# OpenSourceSyringePump.net
KiCad netlist of a schematic drawn in EAGLE
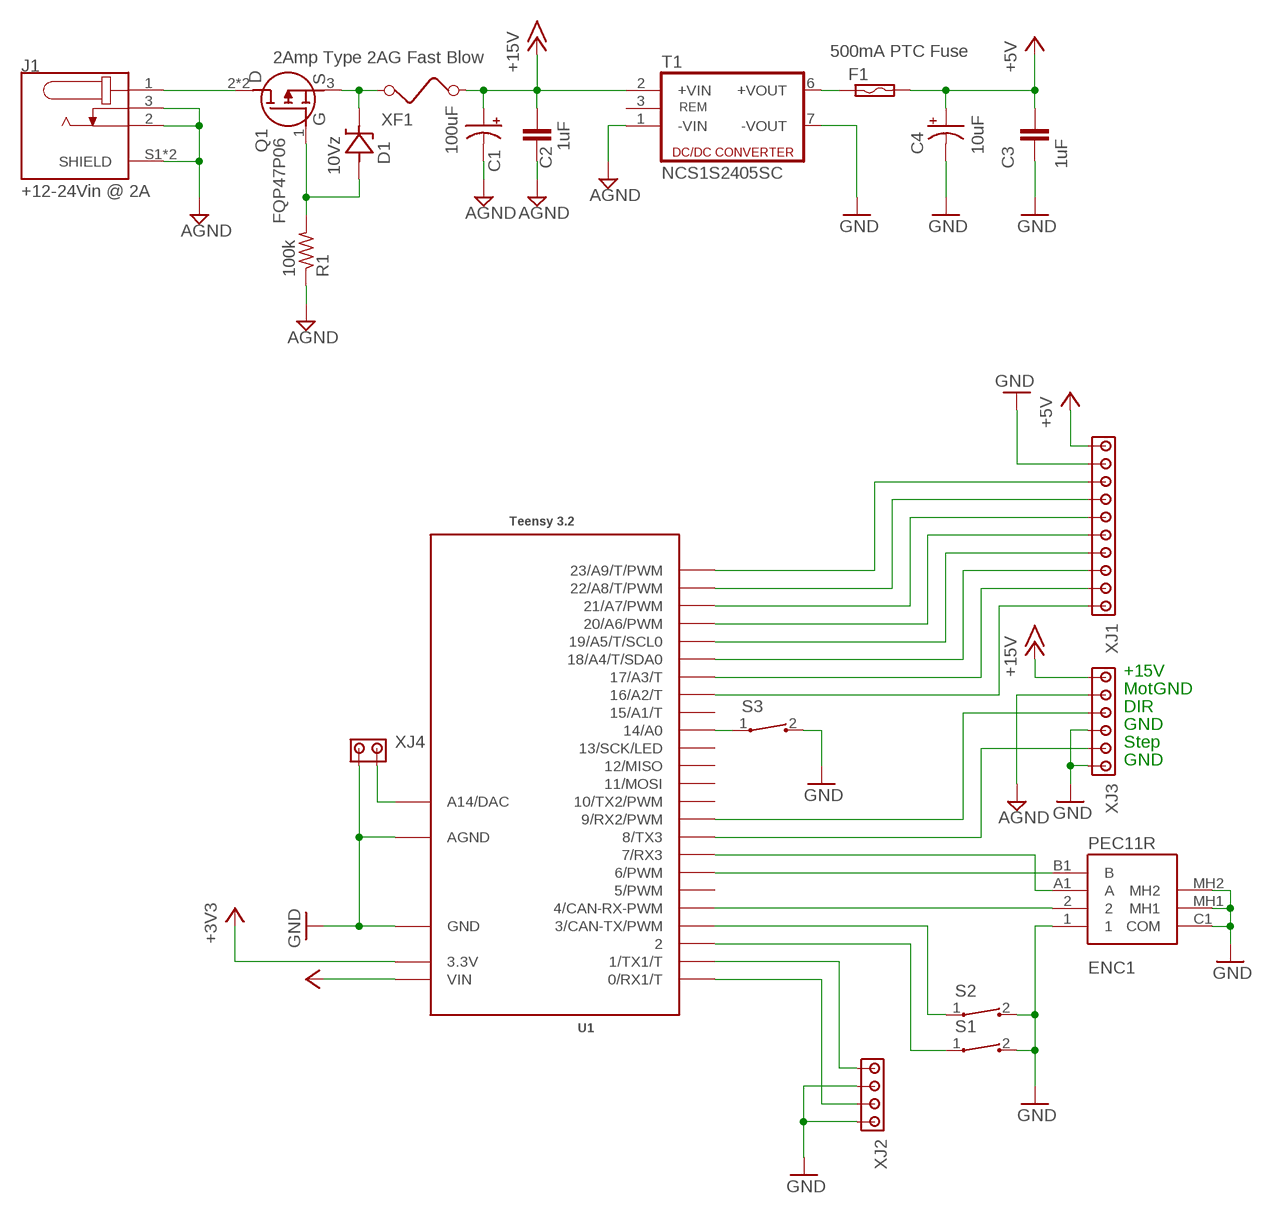
[diagram p0: schematic, sheet 1]

(export (version "E")
  (design (tool "Eeschema 10.0.6"))
  (components
    (comp (ref "C1")
      (value "100uF")
      (footprint "eagle-import:EEUFR1H101")
      (libsource (lib "eagle-import") (part "EEUFR1H101"))
    )
    (comp (ref "C2")
      (value "1uF")
      (footprint "eagle-import:K105Z20Y5VF5TL2")
      (libsource (lib "eagle-import") (part "K105Z20Y5VF5TL2"))
    )
    (comp (ref "C3")
      (value "1uF")
      (footprint "eagle-import:K105Z20Y5VF5TL2")
      (libsource (lib "eagle-import") (part "K105Z20Y5VF5TL2"))
    )
    (comp (ref "C4")
      (value "10uF")
      (footprint "eagle-import:TAP106K025SCS")
      (libsource (lib "eagle-import") (part "TAP106K025SCS"))
    )
    (comp (ref "D1")
      (value "10Vz")
      (footprint "eagle-import:BZX79C10")
      (libsource (lib "eagle-import") (part "BZX79C10"))
    )
    (comp (ref "ENC1")
      (value "PEC11R")
      (footprint "eagle-import:PEC11R4220FS0024")
      (fields
        (field (name "MANUFACTURER_PART_NUMBER") "PEC11R-4220F-S0024")
        (field (name "MOUSER_PART_NUMBER") "652-PEC11R-4220F-S24")
      )
      (libsource (lib "eagle-import") (part "PEC11R-4220F-S0024"))
    )
    (comp (ref "F1")
      (value "500mA PTC Fuse")
      (footprint "eagle-import:BOURNS-MF-R025")
      (libsource (lib "eagle-import") (part "BOURNS-MF-R025"))
    )
    (comp (ref "J1")
      (value "+12-24Vin @ 2A")
      (footprint "eagle-import:CUI_PJ-079AH")
      (fields (field (name "MANUFACTURER") "CUI Inc"))
      (libsource (lib "eagle-import") (part "PJ-079AH"))
    )
    (comp (ref "Q1")
      (value "FQP47P06")
      (footprint "eagle-import:FQP47P06")
      (libsource (lib "eagle-import") (part "FQP47P06"))
    )
    (comp (ref "R1")
      (value "100k")
      (footprint "eagle-import:0204_7")
      (libsource (lib "eagle-import") (part "RESISTOR.25W"))
    )
    (comp (ref "S1")
      (value "ALPS-SKRGAFD010")
      (footprint "eagle-import:ALPS-SKRGAFD010")
      (libsource (lib "eagle-import") (part "ALPS-SKRGAFD010"))
    )
    (comp (ref "S2")
      (value "ALPS-SKRGAFD010")
      (footprint "eagle-import:ALPS-SKRGAFD010")
      (libsource (lib "eagle-import") (part "ALPS-SKRGAFD010"))
    )
    (comp (ref "S3")
      (value "ALPS-SKRGAFD010")
      (footprint "eagle-import:ALPS-SKRGAFD010")
      (libsource (lib "eagle-import") (part "ALPS-SKRGAFD010"))
    )
    (comp (ref "T1")
      (value "NCS1S2405SC")
      (footprint "eagle-import:MURATA-NCS1S2405SC")
      (libsource (lib "eagle-import") (part "MURATA-NCS1S2405SC"))
    )
    (comp (ref "U1")
      (value "Teensy 3.2")
      (footprint "eagle-import:TEENSY_3.0-3.2&LC_OUTER_ROW")
      (libsource (lib "eagle-import") (part "TEENSY_3.1-3.2_OUTER_ROW"))
    )
    (comp (ref "XF1")
      (value "2Amp Type 2AG Fast Blow")
      (footprint "eagle-import:LITTLEFUSE-02540101Z")
      (libsource (lib "eagle-import") (part "LITTLEFUSE-02540101Z"))
    )
    (comp (ref "XJ1")
      (value "TE-1-282834-0-DOUBLE")
      (footprint "eagle-import:TE-1-282834-0-DOUBLE")
      (libsource (lib "eagle-import") (part "TE-1-282834-0-DOUBLE"))
    )
    (comp (ref "XJ2")
      (value "TE-282834-4-DOUBLE")
      (footprint "eagle-import:TE-282834-4-DOUBLE")
      (libsource (lib "eagle-import") (part "TE-282834-4-DOUBLE"))
    )
    (comp (ref "XJ3")
      (value "TE-282834-6-DOUBLE")
      (footprint "eagle-import:TE-282834-6-DOUBLE")
      (libsource (lib "eagle-import") (part "TE-282834-6-DOUBLE"))
    )
    (comp (ref "XJ4")
      (value "TE-282834-2-DOUBLE")
      (footprint "eagle-import:TE-282834-2-DOUBLE")
      (libsource (lib "eagle-import") (part "TE-282834-2-DOUBLE"))
    )
  )
  (nets
    (net (code "1") (name "+3V3") (class "Default")
      (node (ref "U1") (pin "3.3V") (pinfunction "3.3V_3.3V") (pintype "power_in"))
    )
    (net (code "2") (name "+5V") (class "Default")
      (node (ref "C3") (pin "1") (pinfunction "1_1") (pintype "passive"))
      (node (ref "C4") (pin "+") (pinfunction "+_+") (pintype "passive"))
      (node (ref "F1") (pin "2") (pinfunction "2_2") (pintype "passive"))
      (node (ref "U1") (pin "VIN") (pinfunction "VIN_VIN") (pintype "power_in"))
      (node (ref "XJ1") (pin "1") (pinfunction "1_1") (pintype "passive"))
      (node (ref "XJ1") (pin "P$1") (pinfunction "1_P$1") (pintype "passive"))
    )
    (net (code "3") (name "+15V") (class "Default")
      (node (ref "C1") (pin "+") (pinfunction "+_+") (pintype "passive"))
      (node (ref "C2") (pin "1") (pinfunction "1_1") (pintype "passive"))
      (node (ref "T1") (pin "2") (pinfunction "+VIN_2") (pintype "power_in"))
      (node (ref "XF1") (pin "1") (pinfunction "1_1") (pintype "passive"))
      (node (ref "XJ3") (pin "1") (pinfunction "1_1") (pintype "passive"))
      (node (ref "XJ3") (pin "P$1") (pinfunction "1_P$1") (pintype "passive"))
    )
    (net (code "4") (name "AGND") (class "Default")
      (node (ref "C1") (pin "-") (pinfunction "-_-") (pintype "passive"))
      (node (ref "C2") (pin "2") (pinfunction "2_2") (pintype "passive"))
      (node (ref "J1") (pin "2") (pinfunction "2_2") (pintype "passive"))
      (node (ref "J1") (pin "3") (pinfunction "3_3") (pintype "passive"))
      (node (ref "J1") (pin "S1") (pinfunction "SHIELD_S1") (pintype "passive"))
      (node (ref "J1") (pin "S2") (pinfunction "SHIELD_S2") (pintype "passive"))
      (node (ref "R1") (pin "1") (pinfunction "1_1") (pintype "passive"))
      (node (ref "T1") (pin "1") (pinfunction "-VIN_1") (pintype "power_in"))
      (node (ref "XJ3") (pin "2") (pinfunction "2_2") (pintype "passive"))
      (node (ref "XJ3") (pin "P$2") (pinfunction "2_P$2") (pintype "passive"))
    )
    (net (code "5") (name "GND") (class "Default")
      (node (ref "C3") (pin "2") (pinfunction "2_2") (pintype "passive"))
      (node (ref "C4") (pin "-") (pinfunction "-_-") (pintype "passive"))
      (node (ref "ENC1") (pin "1") (pinfunction "1_1") (pintype "bidirectional"))
      (node (ref "ENC1") (pin "C1") (pinfunction "COM_C1") (pintype "power_in"))
      (node (ref "ENC1") (pin "MH1") (pinfunction "MH1_MH1") (pintype "bidirectional"))
      (node (ref "ENC1") (pin "MH2") (pinfunction "MH2_MH2") (pintype "bidirectional"))
      (node (ref "S1") (pin "2") (pinfunction "2_2") (pintype "passive"))
      (node (ref "S2") (pin "2") (pinfunction "2_2") (pintype "passive"))
      (node (ref "S3") (pin "2") (pinfunction "2_2") (pintype "passive"))
      (node (ref "T1") (pin "7") (pinfunction "-VOUT_7") (pintype "power_in"))
      (node (ref "U1") (pin "AGND") (pinfunction "AGND_AGND") (pintype "power_in"))
      (node (ref "U1") (pin "GND") (pinfunction "GND_GND") (pintype "power_in"))
      (node (ref "XJ1") (pin "2") (pinfunction "2_2") (pintype "passive"))
      (node (ref "XJ1") (pin "P$2") (pinfunction "2_P$2") (pintype "passive"))
      (node (ref "XJ2") (pin "2") (pinfunction "2_2") (pintype "passive"))
      (node (ref "XJ2") (pin "4") (pinfunction "4_4") (pintype "passive"))
      (node (ref "XJ2") (pin "P$2") (pinfunction "2_P$2") (pintype "passive"))
      (node (ref "XJ2") (pin "P$4") (pinfunction "4_P$4") (pintype "passive"))
      (node (ref "XJ3") (pin "4") (pinfunction "4_4") (pintype "passive"))
      (node (ref "XJ3") (pin "6") (pinfunction "6_6") (pintype "passive"))
      (node (ref "XJ3") (pin "P$4") (pinfunction "4_P$4") (pintype "passive"))
      (node (ref "XJ3") (pin "P$6") (pinfunction "6_P$6") (pintype "passive"))
      (node (ref "XJ4") (pin "1") (pinfunction "1_1") (pintype "passive"))
      (node (ref "XJ4") (pin "P$1") (pinfunction "1_P$1") (pintype "passive"))
    )
    (net (code "6") (name "Net-(ENC1-A)") (class "Default")
      (node (ref "ENC1") (pin "A1") (pinfunction "A_A1") (pintype "bidirectional"))
      (node (ref "U1") (pin "7") (pinfunction "7/RX3_7") (pintype "bidirectional"))
    )
    (net (code "7") (name "Net-(ENC1-B)") (class "Default")
      (node (ref "ENC1") (pin "B1") (pinfunction "B_B1") (pintype "bidirectional"))
      (node (ref "U1") (pin "6") (pinfunction "6/PWM_6") (pintype "bidirectional"))
    )
    (net (code "8") (name "Net-(J1-Pad1)") (class "Default")
      (node (ref "J1") (pin "1") (pinfunction "1_1") (pintype "passive"))
      (node (ref "Q1") (pin "2") (pinfunction "D_2") (pintype "bidirectional"))
      (node (ref "Q1") (pin "MH") (pinfunction "D_MH") (pintype "bidirectional"))
    )
    (net (code "9") (name "Net-(Q1-G)") (class "Default")
      (node (ref "D1") (pin "A") (pinfunction "A_A") (pintype "passive"))
      (node (ref "Q1") (pin "1") (pinfunction "G_1") (pintype "bidirectional"))
      (node (ref "R1") (pin "2") (pinfunction "2_2") (pintype "passive"))
    )
    (net (code "10") (name "Net-(Q1-S)") (class "Default")
      (node (ref "D1") (pin "C") (pinfunction "C_C") (pintype "passive"))
      (node (ref "Q1") (pin "3") (pinfunction "S_3") (pintype "bidirectional"))
      (node (ref "XF1") (pin "2") (pinfunction "2_2") (pintype "passive"))
    )
    (net (code "11") (name "Net-(S1-Pad1)") (class "Default")
      (node (ref "S1") (pin "1") (pinfunction "1_1") (pintype "passive"))
      (node (ref "U1") (pin "2") (pinfunction "2_2") (pintype "bidirectional"))
    )
    (net (code "12") (name "Net-(S3-Pad1)") (class "Default")
      (node (ref "S3") (pin "1") (pinfunction "1_1") (pintype "passive"))
      (node (ref "U1") (pin "14/A0") (pinfunction "14/A0_14/A0") (pintype "bidirectional"))
    )
    (net (code "13") (name "Net-(T1-+VOUT)") (class "Default")
      (node (ref "F1") (pin "1") (pinfunction "1_1") (pintype "passive"))
      (node (ref "T1") (pin "6") (pinfunction "+VOUT_6") (pintype "power_in"))
    )
    (net (code "14") (name "Net-(U1-0{slash}RX1{slash}T)") (class "Default")
      (node (ref "U1") (pin "0") (pinfunction "0/RX1/T_0") (pintype "bidirectional"))
      (node (ref "XJ2") (pin "3") (pinfunction "3_3") (pintype "passive"))
      (node (ref "XJ2") (pin "P$3") (pinfunction "3_P$3") (pintype "passive"))
    )
    (net (code "15") (name "Net-(U1-1{slash}TX1{slash}T)") (class "Default")
      (node (ref "U1") (pin "1") (pinfunction "1/TX1/T_1") (pintype "bidirectional"))
      (node (ref "XJ2") (pin "1") (pinfunction "1_1") (pintype "passive"))
      (node (ref "XJ2") (pin "P$1") (pinfunction "1_P$1") (pintype "passive"))
    )
    (net (code "16") (name "Net-(U1-3{slash}CAN-TX{slash}PWM)") (class "Default")
      (node (ref "S2") (pin "1") (pinfunction "1_1") (pintype "passive"))
      (node (ref "U1") (pin "3") (pinfunction "3/CAN-TX/PWM_3") (pintype "bidirectional"))
    )
    (net (code "17") (name "Net-(U1-4{slash}CAN-RX-PWM)") (class "Default")
      (node (ref "ENC1") (pin "2") (pinfunction "2_2") (pintype "bidirectional"))
      (node (ref "U1") (pin "4") (pinfunction "4/CAN-RX-PWM_4") (pintype "bidirectional"))
    )
    (net (code "18") (name "Net-(U1-8{slash}TX3)") (class "Default")
      (node (ref "U1") (pin "8") (pinfunction "8/TX3_8") (pintype "bidirectional"))
      (node (ref "XJ3") (pin "5") (pinfunction "5_5") (pintype "passive"))
      (node (ref "XJ3") (pin "P$5") (pinfunction "5_P$5") (pintype "passive"))
    )
    (net (code "19") (name "Net-(U1-9{slash}RX2{slash}PWM)") (class "Default")
      (node (ref "U1") (pin "9") (pinfunction "9/RX2/PWM_9") (pintype "bidirectional"))
      (node (ref "XJ3") (pin "3") (pinfunction "3_3") (pintype "passive"))
      (node (ref "XJ3") (pin "P$3") (pinfunction "3_P$3") (pintype "passive"))
    )
    (net (code "20") (name "Net-(U1-16{slash}A2{slash}T)") (class "Default")
      (node (ref "U1") (pin "16/A2") (pinfunction "16/A2/T_16/A2") (pintype "bidirectional"))
      (node (ref "XJ1") (pin "10") (pinfunction "10_10") (pintype "passive"))
      (node (ref "XJ1") (pin "P$10") (pinfunction "10_P$10") (pintype "passive"))
    )
    (net (code "21") (name "Net-(U1-17{slash}A3{slash}T)") (class "Default")
      (node (ref "U1") (pin "17/A3") (pinfunction "17/A3/T_17/A3") (pintype "bidirectional"))
      (node (ref "XJ1") (pin "9") (pinfunction "9_9") (pintype "passive"))
      (node (ref "XJ1") (pin "P$9") (pinfunction "9_P$9") (pintype "passive"))
    )
    (net (code "22") (name "Net-(U1-18{slash}A4{slash}T{slash}SDA0)") (class "Default")
      (node (ref "U1") (pin "18/A4") (pinfunction "18/A4/T/SDA0_18/A4") (pintype "bidirectional"))
      (node (ref "XJ1") (pin "8") (pinfunction "8_8") (pintype "passive"))
      (node (ref "XJ1") (pin "P$8") (pinfunction "8_P$8") (pintype "passive"))
    )
    (net (code "23") (name "Net-(U1-19{slash}A5{slash}T{slash}SCL0)") (class "Default")
      (node (ref "U1") (pin "19/A5") (pinfunction "19/A5/T/SCL0_19/A5") (pintype "bidirectional"))
      (node (ref "XJ1") (pin "7") (pinfunction "7_7") (pintype "passive"))
      (node (ref "XJ1") (pin "P$7") (pinfunction "7_P$7") (pintype "passive"))
    )
    (net (code "24") (name "Net-(U1-20{slash}A6{slash}PWM)") (class "Default")
      (node (ref "U1") (pin "20/A6") (pinfunction "20/A6/PWM_20/A6") (pintype "bidirectional"))
      (node (ref "XJ1") (pin "6") (pinfunction "6_6") (pintype "passive"))
      (node (ref "XJ1") (pin "P$6") (pinfunction "6_P$6") (pintype "passive"))
    )
    (net (code "25") (name "Net-(U1-21{slash}A7{slash}PWM)") (class "Default")
      (node (ref "U1") (pin "21/A7") (pinfunction "21/A7/PWM_21/A7") (pintype "bidirectional"))
      (node (ref "XJ1") (pin "5") (pinfunction "5_5") (pintype "passive"))
      (node (ref "XJ1") (pin "P$5") (pinfunction "5_P$5") (pintype "passive"))
    )
    (net (code "26") (name "Net-(U1-22{slash}A8{slash}T{slash}PWM)") (class "Default")
      (node (ref "U1") (pin "22/A8") (pinfunction "22/A8/T/PWM_22/A8") (pintype "bidirectional"))
      (node (ref "XJ1") (pin "4") (pinfunction "4_4") (pintype "passive"))
      (node (ref "XJ1") (pin "P$4") (pinfunction "4_P$4") (pintype "passive"))
    )
    (net (code "27") (name "Net-(U1-23{slash}A9{slash}T{slash}PWM)") (class "Default")
      (node (ref "U1") (pin "23/A9") (pinfunction "23/A9/T/PWM_23/A9") (pintype "bidirectional"))
      (node (ref "XJ1") (pin "3") (pinfunction "3_3") (pintype "passive"))
      (node (ref "XJ1") (pin "P$3") (pinfunction "3_P$3") (pintype "passive"))
    )
    (net (code "28") (name "Net-(U1-A14{slash}DAC)") (class "Default")
      (node (ref "U1") (pin "RESET/DAC") (pinfunction "A14/DAC_RESET/DAC") (pintype "bidirectional"))
      (node (ref "XJ4") (pin "2") (pinfunction "2_2") (pintype "passive"))
      (node (ref "XJ4") (pin "P$2") (pinfunction "2_P$2") (pintype "passive"))
    )
    (net (code "29") (name "unconnected-(T1-REM-Pad3)") (class "Default")
      (node (ref "T1") (pin "3") (pinfunction "REM_3") (pintype "bidirectional"))
    )
    (net (code "30") (name "unconnected-(U1-5{slash}PWM-Pad5)") (class "Default")
      (node (ref "U1") (pin "5") (pinfunction "5/PWM_5") (pintype "bidirectional"))
    )
    (net (code "31") (name "unconnected-(U1-10{slash}TX2{slash}PWM-Pad10)") (class "Default")
      (node (ref "U1") (pin "10") (pinfunction "10/TX2/PWM_10") (pintype "bidirectional"))
    )
    (net (code "32") (name "unconnected-(U1-11{slash}MOSI-Pad11)") (class "Default")
      (node (ref "U1") (pin "11") (pinfunction "11/MOSI_11") (pintype "bidirectional"))
    )
    (net (code "33") (name "unconnected-(U1-12{slash}MISO-Pad12)") (class "Default")
      (node (ref "U1") (pin "12") (pinfunction "12/MISO_12") (pintype "bidirectional"))
    )
    (net (code "34") (name "unconnected-(U1-13{slash}SCK{slash}LED-Pad13)") (class "Default")
      (node (ref "U1") (pin "13") (pinfunction "13/SCK/LED_13") (pintype "bidirectional"))
    )
    (net (code "35") (name "unconnected-(U1-15{slash}A1{slash}T-Pad15{slash}A1)") (class "Default")
      (node (ref "U1") (pin "15/A1") (pinfunction "15/A1/T_15/A1") (pintype "bidirectional"))
    )
  )
)
